# opnic.net
KiCad netlist of a schematic drawn in EAGLE
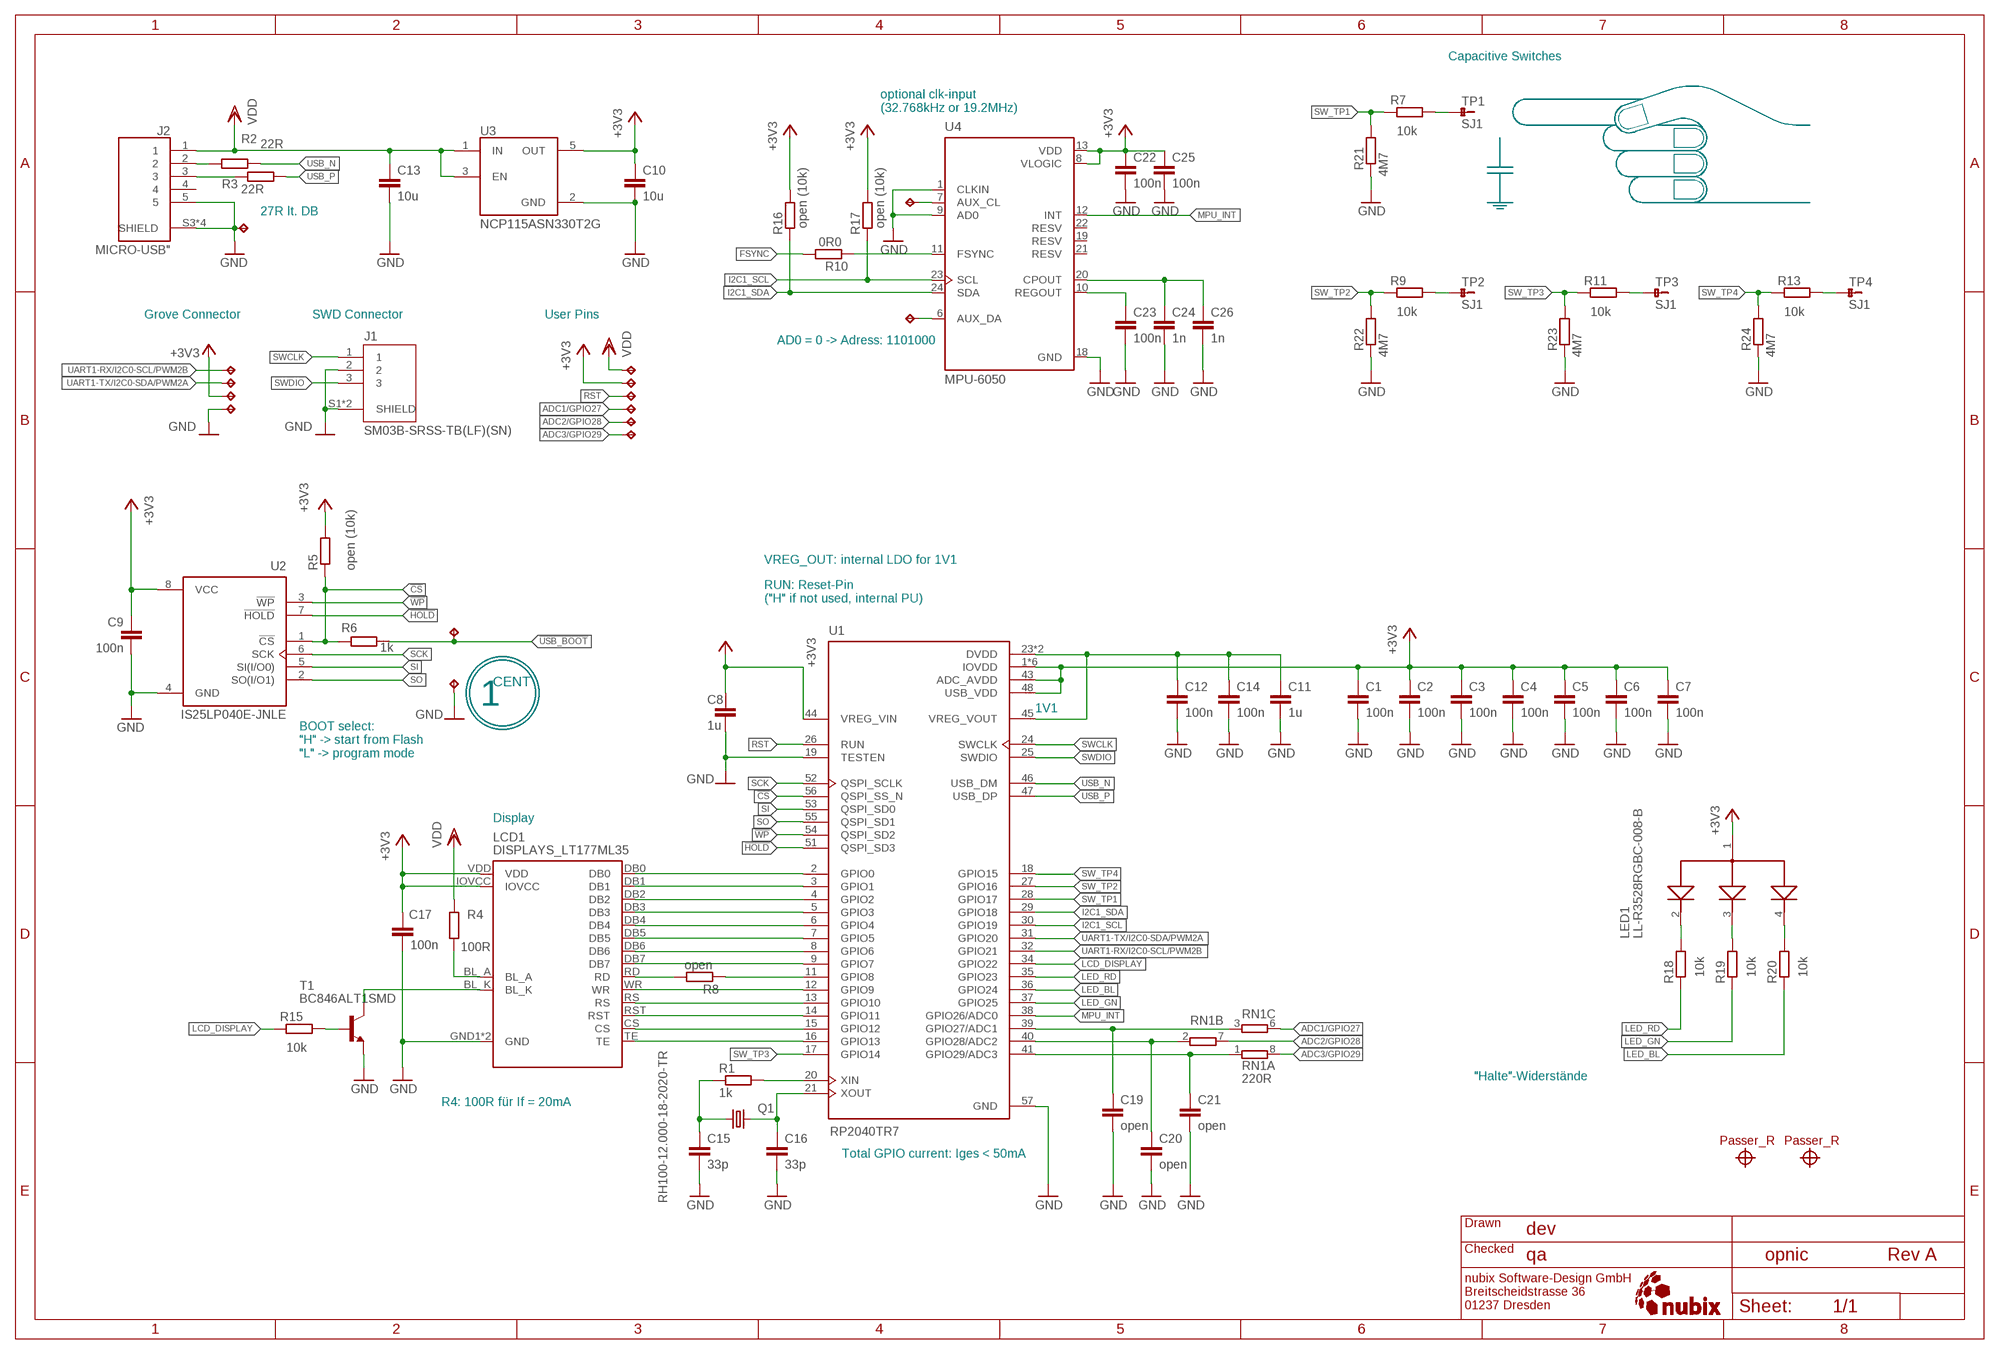
[diagram p0: schematic, sheet 1]

(export (version "E")
  (design (tool "Eeschema 10.0.6"))
  (components
    (comp (ref "3V3")
      (value "TPTP06SQ")
      (footprint "eagle-import:TP06SQ")
      (libsource (lib "eagle-import") (part "TPTP06SQ"))
    )
    (comp (ref "C1")
      (value "100n")
      (footprint "eagle-import:C0603")
      (libsource (lib "eagle-import") (part "C-EUC0603"))
    )
    (comp (ref "C2")
      (value "100n")
      (footprint "eagle-import:C0603")
      (libsource (lib "eagle-import") (part "C-EUC0603"))
    )
    (comp (ref "C3")
      (value "100n")
      (footprint "eagle-import:C0603")
      (libsource (lib "eagle-import") (part "C-EUC0603"))
    )
    (comp (ref "C4")
      (value "100n")
      (footprint "eagle-import:C0603")
      (libsource (lib "eagle-import") (part "C-EUC0603"))
    )
    (comp (ref "C5")
      (value "100n")
      (footprint "eagle-import:C0603")
      (libsource (lib "eagle-import") (part "C-EUC0603"))
    )
    (comp (ref "C6")
      (value "100n")
      (footprint "eagle-import:C0603")
      (libsource (lib "eagle-import") (part "C-EUC0603"))
    )
    (comp (ref "C7")
      (value "100n")
      (footprint "eagle-import:C0603")
      (libsource (lib "eagle-import") (part "C-EUC0603"))
    )
    (comp (ref "C8")
      (value "1u")
      (footprint "eagle-import:C0805")
      (libsource (lib "eagle-import") (part "C-EUC0805"))
    )
    (comp (ref "C9")
      (value "100n")
      (footprint "eagle-import:C0603")
      (libsource (lib "eagle-import") (part "C-EUC0603"))
    )
    (comp (ref "C10")
      (value "10u")
      (footprint "eagle-import:C1206")
      (libsource (lib "eagle-import") (part "C-EUC1206"))
    )
    (comp (ref "C11")
      (value "1u")
      (footprint "eagle-import:C0805")
      (libsource (lib "eagle-import") (part "C-EUC0805"))
    )
    (comp (ref "C12")
      (value "100n")
      (footprint "eagle-import:C0603")
      (libsource (lib "eagle-import") (part "C-EUC0603"))
    )
    (comp (ref "C13")
      (value "10u")
      (footprint "eagle-import:C1206")
      (libsource (lib "eagle-import") (part "C-EUC1206"))
    )
    (comp (ref "C14")
      (value "100n")
      (footprint "eagle-import:C0603")
      (libsource (lib "eagle-import") (part "C-EUC0603"))
    )
    (comp (ref "C15")
      (value "33p")
      (footprint "eagle-import:C0603")
      (libsource (lib "eagle-import") (part "C-EUC0603"))
    )
    (comp (ref "C16")
      (value "33p")
      (footprint "eagle-import:C0603")
      (libsource (lib "eagle-import") (part "C-EUC0603"))
    )
    (comp (ref "C17")
      (value "100n")
      (footprint "eagle-import:C0603")
      (libsource (lib "eagle-import") (part "C-EUC0603"))
    )
    (comp (ref "C19")
      (value "open")
      (footprint "eagle-import:C0603")
      (libsource (lib "eagle-import") (part "C-EUC0603"))
    )
    (comp (ref "C20")
      (value "open")
      (footprint "eagle-import:C0603")
      (libsource (lib "eagle-import") (part "C-EUC0603"))
    )
    (comp (ref "C21")
      (value "open")
      (footprint "eagle-import:C0603")
      (libsource (lib "eagle-import") (part "C-EUC0603"))
    )
    (comp (ref "C22")
      (value "100n")
      (footprint "eagle-import:C0603")
      (libsource (lib "eagle-import") (part "C-EUC0603"))
    )
    (comp (ref "C23")
      (value "100n")
      (footprint "eagle-import:C0603")
      (libsource (lib "eagle-import") (part "C-EUC0603"))
    )
    (comp (ref "C24")
      (value "1n")
      (footprint "eagle-import:C0603")
      (libsource (lib "eagle-import") (part "C-EUC0603"))
    )
    (comp (ref "C25")
      (value "100n")
      (footprint "eagle-import:C0603")
      (libsource (lib "eagle-import") (part "C-EUC0603"))
    )
    (comp (ref "C26")
      (value "1n")
      (footprint "eagle-import:C0603")
      (libsource (lib "eagle-import") (part "C-EUC0603"))
    )
    (comp (ref "CL")
      (value "TPTP15SQ")
      (footprint "eagle-import:TP15SQ")
      (libsource (lib "eagle-import") (part "TPTP15SQ"))
    )
    (comp (ref "DA")
      (value "TPTP15SQ")
      (footprint "eagle-import:TP15SQ")
      (libsource (lib "eagle-import") (part "TPTP15SQ"))
    )
    (comp (ref "GND")
      (value "TPTP06SQ")
      (footprint "eagle-import:TP06SQ")
      (libsource (lib "eagle-import") (part "TPTP06SQ"))
    )
    (comp (ref "J1")
      (value "SM03B-SRSS-TB(LF)(SN)")
      (footprint "eagle-import:JST_SM03B-SRSS-TB(LF)(SN)")
      (fields (field (name "MF") "JST Sales"))
      (libsource (lib "eagle-import") (part "SM03B-SRSS-TB(LF)(SN)"))
    )
    (comp (ref "J2")
      (value "MICRO-USB\"")
      (footprint "eagle-import:MICRO-USB_MIDMOUNT")
      (libsource (lib "eagle-import") (part "MICRO-USB{dblquote}"))
    )
    (comp (ref "LCD1")
      (value "DISPLAYS_LT177ML35")
      (footprint "eagle-import:DISPLAYS_LT177ML35")
      (libsource (lib "eagle-import") (part "DISPLAYS_LT177ML35"))
    )
    (comp (ref "LED1")
      (value "LL-R3528RGBC-008-B")
      (footprint "eagle-import:LED_LL-R3528RGBC-008-B")
      (fields (field (name "MF") "Lucky Light"))
      (libsource (lib "eagle-import") (part "LL-R3528RGBC-008-B"))
    )
    (comp (ref "P27")
      (value "TPTP06SQ")
      (footprint "eagle-import:TP06SQ")
      (libsource (lib "eagle-import") (part "TPTP06SQ"))
    )
    (comp (ref "P28")
      (value "TPTP06SQ")
      (footprint "eagle-import:TP06SQ")
      (libsource (lib "eagle-import") (part "TPTP06SQ"))
    )
    (comp (ref "P29")
      (value "TPTP06SQ")
      (footprint "eagle-import:TP06SQ")
      (libsource (lib "eagle-import") (part "TPTP06SQ"))
    )
    (comp (ref "Q1")
      (value "RH100-12.000-18-2020-TR")
      (footprint "eagle-import:3.2X2.5_KX-7")
      (libsource (lib "eagle-import") (part "KX-7"))
    )
    (comp (ref "R1")
      (value "1k")
      (footprint "eagle-import:R0603")
      (libsource (lib "eagle-import") (part "R-EU_R0603"))
    )
    (comp (ref "R2")
      (value "22R")
      (footprint "eagle-import:R0603")
      (libsource (lib "eagle-import") (part "R-EU_R0603"))
    )
    (comp (ref "R3")
      (value "22R")
      (footprint "eagle-import:R0603")
      (libsource (lib "eagle-import") (part "R-EU_R0603"))
    )
    (comp (ref "R4")
      (value "100R")
      (footprint "eagle-import:R0603")
      (libsource (lib "eagle-import") (part "R-EU_R0603"))
    )
    (comp (ref "R5")
      (value "open (10k)")
      (footprint "eagle-import:R0603")
      (libsource (lib "eagle-import") (part "R-EU_R0603"))
    )
    (comp (ref "R6")
      (value "1k")
      (footprint "eagle-import:R0603")
      (libsource (lib "eagle-import") (part "R-EU_R0603"))
    )
    (comp (ref "R7")
      (value "10k")
      (footprint "eagle-import:R0603")
      (libsource (lib "eagle-import") (part "R-EU_R0603"))
    )
    (comp (ref "R8")
      (value "open")
      (footprint "eagle-import:R0603")
      (libsource (lib "eagle-import") (part "R-EU_R0603"))
    )
    (comp (ref "R9")
      (value "10k")
      (footprint "eagle-import:R0603")
      (libsource (lib "eagle-import") (part "R-EU_R0603"))
    )
    (comp (ref "R10")
      (value "0R0")
      (footprint "eagle-import:R0603")
      (libsource (lib "eagle-import") (part "R-EU_R0603"))
    )
    (comp (ref "R11")
      (value "10k")
      (footprint "eagle-import:R0603")
      (libsource (lib "eagle-import") (part "R-EU_R0603"))
    )
    (comp (ref "R13")
      (value "10k")
      (footprint "eagle-import:R0603")
      (libsource (lib "eagle-import") (part "R-EU_R0603"))
    )
    (comp (ref "R15")
      (value "10k")
      (footprint "eagle-import:R0603")
      (libsource (lib "eagle-import") (part "R-EU_R0603"))
    )
    (comp (ref "R16")
      (value "open (10k)")
      (footprint "eagle-import:R0603")
      (libsource (lib "eagle-import") (part "R-EU_R0603"))
    )
    (comp (ref "R17")
      (value "open (10k)")
      (footprint "eagle-import:R0603")
      (libsource (lib "eagle-import") (part "R-EU_R0603"))
    )
    (comp (ref "R18")
      (value "10k")
      (footprint "eagle-import:R0603")
      (libsource (lib "eagle-import") (part "R-EU_R0603"))
    )
    (comp (ref "R19")
      (value "10k")
      (footprint "eagle-import:R0603")
      (libsource (lib "eagle-import") (part "R-EU_R0603"))
    )
    (comp (ref "R20")
      (value "10k")
      (footprint "eagle-import:R0603")
      (libsource (lib "eagle-import") (part "R-EU_R0603"))
    )
    (comp (ref "R21")
      (value "4M7")
      (footprint "eagle-import:R1206")
      (libsource (lib "eagle-import") (part "R-EU_R1206"))
    )
    (comp (ref "R22")
      (value "4M7")
      (footprint "eagle-import:R1206")
      (libsource (lib "eagle-import") (part "R-EU_R1206"))
    )
    (comp (ref "R23")
      (value "4M7")
      (footprint "eagle-import:R1206")
      (libsource (lib "eagle-import") (part "R-EU_R1206"))
    )
    (comp (ref "R24")
      (value "4M7")
      (footprint "eagle-import:R1206")
      (libsource (lib "eagle-import") (part "R-EU_R1206"))
    )
    (comp (ref "RN1")
      (value "220R")
      (footprint "eagle-import:0603-ARC")
      (libsource (lib "eagle-import") (part "4R-N0603-ARC"))
    )
    (comp (ref "RST")
      (value "TPTP06SQ")
      (footprint "eagle-import:TP06SQ")
      (libsource (lib "eagle-import") (part "TPTP06SQ"))
    )
    (comp (ref "SCL")
      (value "TPTP06SQ")
      (footprint "eagle-import:TP06SQ")
      (libsource (lib "eagle-import") (part "TPTP06SQ"))
    )
    (comp (ref "SDA")
      (value "TPTP06SQ")
      (footprint "eagle-import:TP06SQ")
      (libsource (lib "eagle-import") (part "TPTP06SQ"))
    )
    (comp (ref "T1")
      (value "BC846ALT1SMD")
      (footprint "eagle-import:SOT23")
      (libsource (lib "eagle-import") (part "BC846SMDALT1"))
    )
    (comp (ref "TP1")
      (value "SJ1")
      (footprint "eagle-import:PAD1X1")
      (libsource (lib "eagle-import") (part "SJ1"))
    )
    (comp (ref "TP2")
      (value "SJ1")
      (footprint "eagle-import:PAD1X1")
      (libsource (lib "eagle-import") (part "SJ1"))
    )
    (comp (ref "TP3")
      (value "SJ1")
      (footprint "eagle-import:PAD1X1")
      (libsource (lib "eagle-import") (part "SJ1"))
    )
    (comp (ref "TP4")
      (value "SJ1")
      (footprint "eagle-import:PAD1X1")
      (libsource (lib "eagle-import") (part "SJ1"))
    )
    (comp (ref "TP9")
      (value "TPPAD1-17")
      (footprint "eagle-import:P1-17")
      (libsource (lib "eagle-import") (part "TPPAD1-17"))
    )
    (comp (ref "TP10")
      (value "TPPAD1-17")
      (footprint "eagle-import:P1-17")
      (libsource (lib "eagle-import") (part "TPPAD1-17"))
    )
    (comp (ref "TP11")
      (value "TPTP06SQ")
      (footprint "eagle-import:TP06SQ")
      (libsource (lib "eagle-import") (part "TPTP06SQ"))
    )
    (comp (ref "U$1")
      (value "PASSER_R")
      (footprint "eagle-import:PASSER_RUND")
      (libsource (lib "eagle-import") (part "PASSER_R"))
    )
    (comp (ref "U$2")
      (value "PASSER_R")
      (footprint "eagle-import:PASSER_RUND")
      (libsource (lib "eagle-import") (part "PASSER_R"))
    )
    (comp (ref "U1")
      (value "RP2040TR7")
      (footprint "eagle-import:QFN40P700X700X90-57N")
      (fields (field (name "MF") "Raspberry Pi"))
      (libsource (lib "eagle-import") (part "RP2040TR7"))
    )
    (comp (ref "U2")
      (value "IS25LP040E-JNLE")
      (footprint "eagle-import:SOIC127P599X175-8N")
      (fields (field (name "MF") "Adesto Technologies") (field (name "MP") "AT25SF041B-SSHB-B"))
      (libsource (lib "eagle-import") (part "AT25SF041B-SSHB-B"))
    )
    (comp (ref "U3")
      (value "NCP115ASN330T2G")
      (footprint "eagle-import:SOT95P280X145-5N")
      (fields (field (name "MF") "STMicroelectronics") (field (name "MP") "LD39015M12R"))
      (libsource (lib "eagle-import") (part "LD39015M12R"))
    )
    (comp (ref "U4")
      (value "MPU-6050")
      (footprint "eagle-import:QFN50P400X400X95-24N")
      (fields (field (name "MF") "TDK InvenSense"))
      (libsource (lib "eagle-import") (part "MPU-6050"))
    )
    (comp (ref "VCC1")
      (value "TPTP06SQ")
      (footprint "eagle-import:TP06SQ")
      (libsource (lib "eagle-import") (part "TPTP06SQ"))
    )
    (comp (ref "VCC2")
      (value "TPTP06SQ")
      (footprint "eagle-import:TP06SQ")
      (libsource (lib "eagle-import") (part "TPTP06SQ"))
    )
  )
  (nets
    (net (code "1") (name "+3V3") (class "Default")
      (node (ref "3V3") (pin "TP") (pinfunction "TP_TP") (pintype "input"))
      (node (ref "C1") (pin "1") (pinfunction "1_1") (pintype "passive"))
      (node (ref "C10") (pin "1") (pinfunction "1_1") (pintype "passive"))
      (node (ref "C17") (pin "1") (pinfunction "1_1") (pintype "passive"))
      (node (ref "C2") (pin "1") (pinfunction "1_1") (pintype "passive"))
      (node (ref "C22") (pin "1") (pinfunction "1_1") (pintype "passive"))
      (node (ref "C25") (pin "1") (pinfunction "1_1") (pintype "passive"))
      (node (ref "C3") (pin "1") (pinfunction "1_1") (pintype "passive"))
      (node (ref "C4") (pin "1") (pinfunction "1_1") (pintype "passive"))
      (node (ref "C5") (pin "1") (pinfunction "1_1") (pintype "passive"))
      (node (ref "C6") (pin "1") (pinfunction "1_1") (pintype "passive"))
      (node (ref "C7") (pin "1") (pinfunction "1_1") (pintype "passive"))
      (node (ref "C8") (pin "1") (pinfunction "1_1") (pintype "passive"))
      (node (ref "C9") (pin "1") (pinfunction "1_1") (pintype "passive"))
      (node (ref "LCD1") (pin "IOVCC") (pinfunction "IOVCC_IOVCC") (pintype "power_in"))
      (node (ref "LCD1") (pin "VDD") (pinfunction "VDD_VDD") (pintype "power_in"))
      (node (ref "LED1") (pin "1") (pinfunction "COMM_ANODE_1") (pintype "passive"))
      (node (ref "R16") (pin "2") (pinfunction "2_2") (pintype "passive"))
      (node (ref "R17") (pin "2") (pinfunction "2_2") (pintype "passive"))
      (node (ref "R5") (pin "2") (pinfunction "2_2") (pintype "passive"))
      (node (ref "U1") (pin "1") (pinfunction "IOVDD_1") (pintype "power_in"))
      (node (ref "U1") (pin "10") (pinfunction "IOVDD_10") (pintype "power_in"))
      (node (ref "U1") (pin "22") (pinfunction "IOVDD_22") (pintype "power_in"))
      (node (ref "U1") (pin "33") (pinfunction "IOVDD_33") (pintype "power_in"))
      (node (ref "U1") (pin "42") (pinfunction "IOVDD_42") (pintype "power_in"))
      (node (ref "U1") (pin "43") (pinfunction "ADC_AVDD_43") (pintype "power_in"))
      (node (ref "U1") (pin "44") (pinfunction "VREG_VIN_44") (pintype "input"))
      (node (ref "U1") (pin "48") (pinfunction "USB_VDD_48") (pintype "power_in"))
      (node (ref "U1") (pin "49") (pinfunction "IOVDD_49") (pintype "power_in"))
      (node (ref "U2") (pin "8") (pinfunction "VCC_8") (pintype "power_in"))
      (node (ref "U3") (pin "5") (pinfunction "OUT_5") (pintype "output"))
      (node (ref "U4") (pin "13") (pinfunction "VDD_13") (pintype "power_in"))
      (node (ref "U4") (pin "8") (pinfunction "VLOGIC_8") (pintype "power_in"))
      (node (ref "VCC1") (pin "TP") (pinfunction "TP_TP") (pintype "input"))
    )
    (net (code "2") (name "/~{CS}") (class "Default")
      (node (ref "R5") (pin "1") (pinfunction "1_1") (pintype "passive"))
      (node (ref "R6") (pin "2") (pinfunction "2_2") (pintype "passive"))
      (node (ref "U1") (pin "56") (pinfunction "QSPI_SS_N_56") (pintype "bidirectional"))
      (node (ref "U2") (pin "1") (pinfunction "~{CS}_1") (pintype "input"))
    )
    (net (code "3") (name "/~{HOLD}") (class "Default")
      (node (ref "U1") (pin "51") (pinfunction "QSPI_SD3_51") (pintype "bidirectional"))
      (node (ref "U2") (pin "7") (pinfunction "~{HOLD}_7") (pintype "input"))
    )
    (net (code "4") (name "/~{USB_BOOT}") (class "Default")
      (node (ref "R6") (pin "1") (pinfunction "1_1") (pintype "passive"))
      (node (ref "TP9") (pin "TP") (pinfunction "TP_TP") (pintype "input"))
    )
    (net (code "5") (name "/~{WP}") (class "Default")
      (node (ref "U1") (pin "54") (pinfunction "QSPI_SD2_54") (pintype "bidirectional"))
      (node (ref "U2") (pin "3") (pinfunction "~{WP}_3") (pintype "input"))
    )
    (net (code "6") (name "ADC1{slash}GPIO27") (class "Default")
      (node (ref "P27") (pin "TP") (pinfunction "TP_TP") (pintype "input"))
      (node (ref "RN1") (pin "6") (pinfunction "2_6") (pintype "passive"))
    )
    (net (code "7") (name "ADC2{slash}GPIO28") (class "Default")
      (node (ref "P28") (pin "TP") (pinfunction "TP_TP") (pintype "input"))
      (node (ref "RN1") (pin "7") (pinfunction "2_7") (pintype "passive"))
    )
    (net (code "8") (name "ADC3{slash}GPIO29") (class "Default")
      (node (ref "P29") (pin "TP") (pinfunction "TP_TP") (pintype "input"))
      (node (ref "RN1") (pin "8") (pinfunction "2_8") (pintype "passive"))
    )
    (net (code "9") (name "FSYNC") (class "Default")
      (node (ref "R10") (pin "2") (pinfunction "2_2") (pintype "passive"))
      (node (ref "R8") (pin "1") (pinfunction "1_1") (pintype "passive"))
      (node (ref "U1") (pin "11") (pinfunction "GPIO8_11") (pintype "bidirectional"))
    )
    (net (code "10") (name "GND") (class "Default")
      (node (ref "C1") (pin "2") (pinfunction "2_2") (pintype "passive"))
      (node (ref "C10") (pin "2") (pinfunction "2_2") (pintype "passive"))
      (node (ref "C11") (pin "2") (pinfunction "2_2") (pintype "passive"))
      (node (ref "C12") (pin "2") (pinfunction "2_2") (pintype "passive"))
      (node (ref "C13") (pin "2") (pinfunction "2_2") (pintype "passive"))
      (node (ref "C14") (pin "2") (pinfunction "2_2") (pintype "passive"))
      (node (ref "C15") (pin "2") (pinfunction "2_2") (pintype "passive"))
      (node (ref "C16") (pin "2") (pinfunction "2_2") (pintype "passive"))
      (node (ref "C17") (pin "2") (pinfunction "2_2") (pintype "passive"))
      (node (ref "C19") (pin "2") (pinfunction "2_2") (pintype "passive"))
      (node (ref "C2") (pin "2") (pinfunction "2_2") (pintype "passive"))
      (node (ref "C20") (pin "2") (pinfunction "2_2") (pintype "passive"))
      (node (ref "C21") (pin "2") (pinfunction "2_2") (pintype "passive"))
      (node (ref "C22") (pin "2") (pinfunction "2_2") (pintype "passive"))
      (node (ref "C23") (pin "2") (pinfunction "2_2") (pintype "passive"))
      (node (ref "C24") (pin "2") (pinfunction "2_2") (pintype "passive"))
      (node (ref "C25") (pin "2") (pinfunction "2_2") (pintype "passive"))
      (node (ref "C26") (pin "2") (pinfunction "2_2") (pintype "passive"))
      (node (ref "C3") (pin "2") (pinfunction "2_2") (pintype "passive"))
      (node (ref "C4") (pin "2") (pinfunction "2_2") (pintype "passive"))
      (node (ref "C5") (pin "2") (pinfunction "2_2") (pintype "passive"))
      (node (ref "C6") (pin "2") (pinfunction "2_2") (pintype "passive"))
      (node (ref "C7") (pin "2") (pinfunction "2_2") (pintype "passive"))
      (node (ref "C8") (pin "2") (pinfunction "2_2") (pintype "passive"))
      (node (ref "C9") (pin "2") (pinfunction "2_2") (pintype "passive"))
      (node (ref "GND") (pin "TP") (pinfunction "TP_TP") (pintype "input"))
      (node (ref "J1") (pin "2") (pinfunction "2_2") (pintype "passive"))
      (node (ref "J1") (pin "S1") (pinfunction "SHIELD_S1") (pintype "passive"))
      (node (ref "J1") (pin "S2") (pinfunction "SHIELD_S2") (pintype "passive"))
      (node (ref "J2") (pin "5") (pinfunction "5_5") (pintype "passive"))
      (node (ref "J2") (pin "S3") (pinfunction "SHIELD_S3") (pintype "passive"))
      (node (ref "J2") (pin "S4") (pinfunction "SHIELD_S4") (pintype "passive"))
      (node (ref "J2") (pin "S5") (pinfunction "SHIELD_S5") (pintype "passive"))
      (node (ref "J2") (pin "S6") (pinfunction "SHIELD_S6") (pintype "passive"))
      (node (ref "LCD1") (pin "GND1") (pinfunction "GND_GND1") (pintype "power_in"))
      (node (ref "LCD1") (pin "GND2") (pinfunction "GND_GND2") (pintype "power_in"))
      (node (ref "R21") (pin "1") (pinfunction "1_1") (pintype "passive"))
      (node (ref "R22") (pin "1") (pinfunction "1_1") (pintype "passive"))
      (node (ref "R23") (pin "1") (pinfunction "1_1") (pintype "passive"))
      (node (ref "R24") (pin "1") (pinfunction "1_1") (pintype "passive"))
      (node (ref "T1") (pin "2") (pinfunction "E_2") (pintype "passive"))
      (node (ref "TP10") (pin "TP") (pinfunction "TP_TP") (pintype "input"))
      (node (ref "TP11") (pin "TP") (pinfunction "TP_TP") (pintype "input"))
      (node (ref "U1") (pin "19") (pinfunction "TESTEN_19") (pintype "input"))
      (node (ref "U1") (pin "57") (pinfunction "GND_57") (pintype "power_in"))
      (node (ref "U2") (pin "4") (pinfunction "GND_4") (pintype "power_in"))
      (node (ref "U3") (pin "2") (pinfunction "GND_2") (pintype "power_in"))
      (node (ref "U4") (pin "1") (pinfunction "CLKIN_1") (pintype "input"))
      (node (ref "U4") (pin "18") (pinfunction "GND_18") (pintype "power_in"))
      (node (ref "U4") (pin "9") (pinfunction "AD0_9") (pintype "input"))
    )
    (net (code "11") (name "I2C1_SCL") (class "Default")
      (node (ref "R17") (pin "1") (pinfunction "1_1") (pintype "passive"))
      (node (ref "U1") (pin "30") (pinfunction "GPIO19_30") (pintype "bidirectional"))
      (node (ref "U4") (pin "23") (pinfunction "SCL_23") (pintype "input"))
    )
    (net (code "12") (name "I2C1_SDA") (class "Default")
      (node (ref "R16") (pin "1") (pinfunction "1_1") (pintype "passive"))
      (node (ref "U1") (pin "29") (pinfunction "GPIO18_29") (pintype "bidirectional"))
      (node (ref "U4") (pin "24") (pinfunction "SDA_24") (pintype "bidirectional"))
    )
    (net (code "13") (name "LCD_DISPLAY") (class "Default")
      (node (ref "R15") (pin "1") (pinfunction "1_1") (pintype "passive"))
      (node (ref "U1") (pin "34") (pinfunction "GPIO22_34") (pintype "bidirectional"))
    )
    (net (code "14") (name "LED_BL") (class "Default")
      (node (ref "R20") (pin "1") (pinfunction "1_1") (pintype "passive"))
      (node (ref "U1") (pin "36") (pinfunction "GPIO24_36") (pintype "bidirectional"))
    )
    (net (code "15") (name "LED_GN") (class "Default")
      (node (ref "R19") (pin "1") (pinfunction "1_1") (pintype "passive"))
      (node (ref "U1") (pin "37") (pinfunction "GPIO25_37") (pintype "bidirectional"))
    )
    (net (code "16") (name "LED_RD") (class "Default")
      (node (ref "R18") (pin "1") (pinfunction "1_1") (pintype "passive"))
      (node (ref "U1") (pin "35") (pinfunction "GPIO23_35") (pintype "bidirectional"))
    )
    (net (code "17") (name "MPU_INT") (class "Default")
      (node (ref "U1") (pin "38") (pinfunction "GPIO26/ADC0_38") (pintype "bidirectional"))
      (node (ref "U4") (pin "12") (pinfunction "INT_12") (pintype "output"))
    )
    (net (code "18") (name "Net-(C15-Pad1)") (class "Default")
      (node (ref "C15") (pin "1") (pinfunction "1_1") (pintype "passive"))
      (node (ref "Q1") (pin "1") (pinfunction "1_1") (pintype "passive"))
      (node (ref "R1") (pin "1") (pinfunction "1_1") (pintype "passive"))
    )
    (net (code "19") (name "Net-(J2-Pad2)") (class "Default")
      (node (ref "J2") (pin "2") (pinfunction "2_2") (pintype "passive"))
      (node (ref "R2") (pin "1") (pinfunction "1_1") (pintype "passive"))
    )
    (net (code "20") (name "Net-(J2-Pad3)") (class "Default")
      (node (ref "J2") (pin "3") (pinfunction "3_3") (pintype "passive"))
      (node (ref "R3") (pin "1") (pinfunction "1_1") (pintype "passive"))
    )
    (net (code "21") (name "Net-(LCD1-PadBL_A)") (class "Default")
      (node (ref "LCD1") (pin "BL_A") (pinfunction "BL_A_BL_A") (pintype "power_in"))
      (node (ref "R4") (pin "1") (pinfunction "1_1") (pintype "passive"))
    )
    (net (code "22") (name "Net-(LCD1-PadRD)") (class "Default")
      (node (ref "LCD1") (pin "RD") (pinfunction "RD_RD") (pintype "input"))
      (node (ref "R8") (pin "2") (pinfunction "2_2") (pintype "passive"))
    )
    (net (code "23") (name "Net-(LED1-CATHODE_BLUE)") (class "Default")
      (node (ref "LED1") (pin "4") (pinfunction "CATHODE_BLUE_4") (pintype "passive"))
      (node (ref "R20") (pin "2") (pinfunction "2_2") (pintype "passive"))
    )
    (net (code "24") (name "Net-(LED1-CATHODE_GREEN)") (class "Default")
      (node (ref "LED1") (pin "3") (pinfunction "CATHODE_GREEN_3") (pintype "passive"))
      (node (ref "R19") (pin "2") (pinfunction "2_2") (pintype "passive"))
    )
    (net (code "25") (name "Net-(LED1-CATHODE_RED)") (class "Default")
      (node (ref "LED1") (pin "2") (pinfunction "CATHODE_RED_2") (pintype "passive"))
      (node (ref "R18") (pin "2") (pinfunction "2_2") (pintype "passive"))
    )
    (net (code "26") (name "Net-(Q1-2)") (class "Default")
      (node (ref "C16") (pin "1") (pinfunction "1_1") (pintype "passive"))
      (node (ref "Q1") (pin "3") (pinfunction "2_3") (pintype "passive"))
      (node (ref "U1") (pin "21") (pinfunction "XOUT_21") (pintype "output"))
    )
    (net (code "27") (name "Net-(RN1B-1)") (class "Default")
      (node (ref "C20") (pin "1") (pinfunction "1_1") (pintype "passive"))
      (node (ref "RN1") (pin "2") (pinfunction "1_2") (pintype "passive"))
      (node (ref "U1") (pin "40") (pinfunction "GPIO28/ADC2_40") (pintype "bidirectional"))
    )
    (net (code "28") (name "Net-(RN1C-1)") (class "Default")
      (node (ref "C19") (pin "1") (pinfunction "1_1") (pintype "passive"))
      (node (ref "RN1") (pin "3") (pinfunction "1_3") (pintype "passive"))
      (node (ref "U1") (pin "39") (pinfunction "GPIO27/ADC1_39") (pintype "bidirectional"))
    )
    (net (code "29") (name "Net-(T1-B)") (class "Default")
      (node (ref "R15") (pin "2") (pinfunction "2_2") (pintype "passive"))
      (node (ref "T1") (pin "1") (pinfunction "B_1") (pintype "passive"))
    )
    (net (code "30") (name "Net-(T1-C)") (class "Default")
      (node (ref "LCD1") (pin "BL_K") (pinfunction "BL_K_BL_K") (pintype "power_in"))
      (node (ref "T1") (pin "3") (pinfunction "C_3") (pintype "passive"))
    )
    (net (code "31") (name "Net-(TP1-1)") (class "Default")
      (node (ref "R7") (pin "2") (pinfunction "2_2") (pintype "passive"))
      (node (ref "TP1") (pin "P$1") (pinfunction "1_P$1") (pintype "passive"))
    )
    (net (code "32") (name "Net-(TP2-1)") (class "Default")
      (node (ref "R9") (pin "2") (pinfunction "2_2") (pintype "passive"))
      (node (ref "TP2") (pin "P$1") (pinfunction "1_P$1") (pintype "passive"))
    )
    (net (code "33") (name "Net-(TP3-1)") (class "Default")
      (node (ref "R11") (pin "2") (pinfunction "2_2") (pintype "passive"))
      (node (ref "TP3") (pin "P$1") (pinfunction "1_P$1") (pintype "passive"))
    )
    (net (code "34") (name "Net-(TP4-1)") (class "Default")
      (node (ref "R13") (pin "2") (pinfunction "2_2") (pintype "passive"))
      (node (ref "TP4") (pin "P$1") (pinfunction "1_P$1") (pintype "passive"))
    )
    (net (code "35") (name "Net-(U1-GPIO0)") (class "Default")
      (node (ref "LCD1") (pin "DB0") (pinfunction "DB0_DB0") (pintype "input"))
      (node (ref "U1") (pin "2") (pinfunction "GPIO0_2") (pintype "bidirectional"))
    )
    (net (code "36") (name "Net-(U1-GPIO1)") (class "Default")
      (node (ref "LCD1") (pin "DB1") (pinfunction "DB1_DB1") (pintype "input"))
      (node (ref "U1") (pin "3") (pinfunction "GPIO1_3") (pintype "bidirectional"))
    )
    (net (code "37") (name "Net-(U1-GPIO2)") (class "Default")
      (node (ref "LCD1") (pin "DB2") (pinfunction "DB2_DB2") (pintype "input"))
      (node (ref "U1") (pin "4") (pinfunction "GPIO2_4") (pintype "bidirectional"))
    )
    (net (code "38") (name "Net-(U1-GPIO3)") (class "Default")
      (node (ref "LCD1") (pin "DB3") (pinfunction "DB3_DB3") (pintype "input"))
      (node (ref "U1") (pin "5") (pinfunction "GPIO3_5") (pintype "bidirectional"))
    )
    (net (code "39") (name "Net-(U1-GPIO4)") (class "Default")
      (node (ref "LCD1") (pin "DB4") (pinfunction "DB4_DB4") (pintype "input"))
      (node (ref "U1") (pin "6") (pinfunction "GPIO4_6") (pintype "bidirectional"))
    )
    (net (code "40") (name "Net-(U1-GPIO5)") (class "Default")
      (node (ref "LCD1") (pin "DB5") (pinfunction "DB5_DB5") (pintype "input"))
      (node (ref "U1") (pin "7") (pinfunction "GPIO5_7") (pintype "bidirectional"))
    )
    (net (code "41") (name "Net-(U1-GPIO6)") (class "Default")
      (node (ref "LCD1") (pin "DB6") (pinfunction "DB6_DB6") (pintype "input"))
      (node (ref "U1") (pin "8") (pinfunction "GPIO6_8") (pintype "bidirectional"))
    )
    (net (code "42") (name "Net-(U1-GPIO7)") (class "Default")
      (node (ref "LCD1") (pin "DB7") (pinfunction "DB7_DB7") (pintype "input"))
      (node (ref "U1") (pin "9") (pinfunction "GPIO7_9") (pintype "bidirectional"))
    )
    (net (code "43") (name "Net-(U1-GPIO9)") (class "Default")
      (node (ref "LCD1") (pin "WR") (pinfunction "WR_WR") (pintype "input"))
      (node (ref "U1") (pin "12") (pinfunction "GPIO9_12") (pintype "bidirectional"))
    )
    (net (code "44") (name "Net-(U1-GPIO10)") (class "Default")
      (node (ref "LCD1") (pin "RS") (pinfunction "RS_RS") (pintype "input"))
      (node (ref "U1") (pin "13") (pinfunction "GPIO10_13") (pintype "bidirectional"))
    )
    (net (code "45") (name "Net-(U1-GPIO11)") (class "Default")
      (node (ref "LCD1") (pin "RST") (pinfunction "RST_RST") (pintype "input"))
      (node (ref "U1") (pin "14") (pinfunction "GPIO11_14") (pintype "bidirectional"))
    )
    (net (code "46") (name "Net-(U1-GPIO12)") (class "Default")
      (node (ref "LCD1") (pin "CS") (pinfunction "CS_CS") (pintype "input"))
      (node (ref "U1") (pin "15") (pinfunction "GPIO12_15") (pintype "bidirectional"))
    )
    (net (code "47") (name "Net-(U1-GPIO13)") (class "Default")
      (node (ref "LCD1") (pin "TE") (pinfunction "TE_TE") (pintype "output"))
      (node (ref "U1") (pin "16") (pinfunction "GPIO13_16") (pintype "bidirectional"))
    )
    (net (code "48") (name "Net-(U1-GPIO29{slash}ADC3)") (class "Default")
      (node (ref "C21") (pin "1") (pinfunction "1_1") (pintype "passive"))
      (node (ref "RN1") (pin "1") (pinfunction "1_1") (pintype "passive"))
      (node (ref "U1") (pin "41") (pinfunction "GPIO29/ADC3_41") (pintype "bidirectional"))
    )
    (net (code "49") (name "Net-(U1-VREG_VOUT)") (class "Default")
      (node (ref "C11") (pin "1") (pinfunction "1_1") (pintype "passive"))
      (node (ref "C12") (pin "1") (pinfunction "1_1") (pintype "passive"))
      (node (ref "C14") (pin "1") (pinfunction "1_1") (pintype "passive"))
      (node (ref "U1") (pin "23") (pinfunction "DVDD_23") (pintype "power_in"))
      (node (ref "U1") (pin "45") (pinfunction "VREG_VOUT_45") (pintype "output"))
      (node (ref "U1") (pin "50") (pinfunction "DVDD_50") (pintype "power_in"))
    )
    (net (code "50") (name "Net-(U1-XIN)") (class "Default")
      (node (ref "R1") (pin "2") (pinfunction "2_2") (pintype "passive"))
      (node (ref "U1") (pin "20") (pinfunction "XIN_20") (pintype "input"))
    )
    (net (code "51") (name "Net-(U4-AUX_CL)") (class "Default")
      (node (ref "CL") (pin "TP") (pinfunction "TP_TP") (pintype "input"))
      (node (ref "U4") (pin "7") (pinfunction "AUX_CL_7") (pintype "input"))
    )
    (net (code "52") (name "Net-(U4-AUX_DA)") (class "Default")
      (node (ref "DA") (pin "TP") (pinfunction "TP_TP") (pintype "input"))
      (node (ref "U4") (pin "6") (pinfunction "AUX_DA_6") (pintype "bidirectional"))
    )
    (net (code "53") (name "Net-(U4-CPOUT)") (class "Default")
      (node (ref "C24") (pin "1") (pinfunction "1_1") (pintype "passive"))
      (node (ref "C26") (pin "1") (pinfunction "1_1") (pintype "passive"))
      (node (ref "U4") (pin "20") (pinfunction "CPOUT_20") (pintype "passive"))
    )
    (net (code "54") (name "Net-(U4-FSYNC)") (class "Default")
      (node (ref "R10") (pin "1") (pinfunction "1_1") (pintype "passive"))
      (node (ref "U4") (pin "11") (pinfunction "FSYNC_11") (pintype "input"))
    )
    (net (code "55") (name "Net-(U4-REGOUT)") (class "Default")
      (node (ref "C23") (pin "1") (pinfunction "1_1") (pintype "passive"))
      (node (ref "U4") (pin "10") (pinfunction "REGOUT_10") (pintype "passive"))
    )
    (net (code "56") (name "RST") (class "Default")
      (node (ref "RST") (pin "TP") (pinfunction "TP_TP") (pintype "input"))
      (node (ref "U1") (pin "26") (pinfunction "RUN_26") (pintype "input"))
    )
    (net (code "57") (name "SCK") (class "Default")
      (node (ref "U1") (pin "52") (pinfunction "QSPI_SCLK_52") (pintype "bidirectional"))
      (node (ref "U2") (pin "6") (pinfunction "SCK_6") (pintype "input"))
    )
    (net (code "58") (name "SI") (class "Default")
      (node (ref "U1") (pin "53") (pinfunction "QSPI_SD0_53") (pintype "bidirectional"))
      (node (ref "U2") (pin "5") (pinfunction "SI(I/O0)_5") (pintype "bidirectional"))
    )
    (net (code "59") (name "SO") (class "Default")
      (node (ref "U1") (pin "55") (pinfunction "QSPI_SD1_55") (pintype "bidirectional"))
      (node (ref "U2") (pin "2") (pinfunction "SO(I/O1)_2") (pintype "bidirectional"))
    )
    (net (code "60") (name "SWCLK") (class "Default")
      (node (ref "J1") (pin "1") (pinfunction "1_1") (pintype "passive"))
      (node (ref "U1") (pin "24") (pinfunction "SWCLK_24") (pintype "input"))
    )
    (net (code "61") (name "SWDIO") (class "Default")
      (node (ref "J1") (pin "3") (pinfunction "3_3") (pintype "passive"))
      (node (ref "U1") (pin "25") (pinfunction "SWDIO_25") (pintype "bidirectional"))
    )
    (net (code "62") (name "SW_TP1") (class "Default")
      (node (ref "R21") (pin "2") (pinfunction "2_2") (pintype "passive"))
      (node (ref "R7") (pin "1") (pinfunction "1_1") (pintype "passive"))
      (node (ref "U1") (pin "28") (pinfunction "GPIO17_28") (pintype "bidirectional"))
    )
    (net (code "63") (name "SW_TP2") (class "Default")
      (node (ref "R22") (pin "2") (pinfunction "2_2") (pintype "passive"))
      (node (ref "R9") (pin "1") (pinfunction "1_1") (pintype "passive"))
      (node (ref "U1") (pin "27") (pinfunction "GPIO16_27") (pintype "bidirectional"))
    )
    (net (code "64") (name "SW_TP3") (class "Default")
      (node (ref "R11") (pin "1") (pinfunction "1_1") (pintype "passive"))
      (node (ref "R23") (pin "2") (pinfunction "2_2") (pintype "passive"))
      (node (ref "U1") (pin "17") (pinfunction "GPIO14_17") (pintype "bidirectional"))
    )
    (net (code "65") (name "SW_TP4") (class "Default")
      (node (ref "R13") (pin "1") (pinfunction "1_1") (pintype "passive"))
      (node (ref "R24") (pin "2") (pinfunction "2_2") (pintype "passive"))
      (node (ref "U1") (pin "18") (pinfunction "GPIO15_18") (pintype "bidirectional"))
    )
    (net (code "66") (name "UART1-RX{slash}I2C0-SCL{slash}PWM2B") (class "Default")
      (node (ref "SCL") (pin "TP") (pinfunction "TP_TP") (pintype "input"))
      (node (ref "U1") (pin "32") (pinfunction "GPIO21_32") (pintype "bidirectional"))
    )
    (net (code "67") (name "UART1-TX{slash}I2C0-SDA{slash}PWM2A") (class "Default")
      (node (ref "SDA") (pin "TP") (pinfunction "TP_TP") (pintype "input"))
      (node (ref "U1") (pin "31") (pinfunction "GPIO20_31") (pintype "bidirectional"))
    )
    (net (code "68") (name "USB_N") (class "Default")
      (node (ref "R2") (pin "2") (pinfunction "2_2") (pintype "passive"))
      (node (ref "U1") (pin "46") (pinfunction "USB_DM_46") (pintype "bidirectional"))
    )
    (net (code "69") (name "USB_P") (class "Default")
      (node (ref "R3") (pin "2") (pinfunction "2_2") (pintype "passive"))
      (node (ref "U1") (pin "47") (pinfunction "USB_DP_47") (pintype "bidirectional"))
    )
    (net (code "70") (name "VDD") (class "Default")
      (node (ref "C13") (pin "1") (pinfunction "1_1") (pintype "passive"))
      (node (ref "J2") (pin "1") (pinfunction "1_1") (pintype "passive"))
      (node (ref "R4") (pin "2") (pinfunction "2_2") (pintype "passive"))
      (node (ref "U3") (pin "1") (pinfunction "IN_1") (pintype "input"))
      (node (ref "U3") (pin "3") (pinfunction "EN_3") (pintype "input"))
      (node (ref "VCC2") (pin "TP") (pinfunction "TP_TP") (pintype "input"))
    )
    (net (code "71") (name "unconnected-(J2-Pad4)") (class "Default")
      (node (ref "J2") (pin "4") (pinfunction "4_4") (pintype "passive"))
    )
    (net (code "72") (name "unconnected-(U4-RESV-Pad19)") (class "Default")
      (node (ref "U4") (pin "19") (pinfunction "RESV_19") (pintype "passive"))
    )
    (net (code "73") (name "unconnected-(U4-RESV-Pad21)") (class "Default")
      (node (ref "U4") (pin "21") (pinfunction "RESV_21") (pintype "passive"))
    )
    (net (code "74") (name "unconnected-(U4-RESV-Pad22)") (class "Default")
      (node (ref "U4") (pin "22") (pinfunction "RESV_22") (pintype "passive"))
    )
  )
)
